# NoiseGen_1.net
KiCad netlist of a schematic drawn in EAGLE
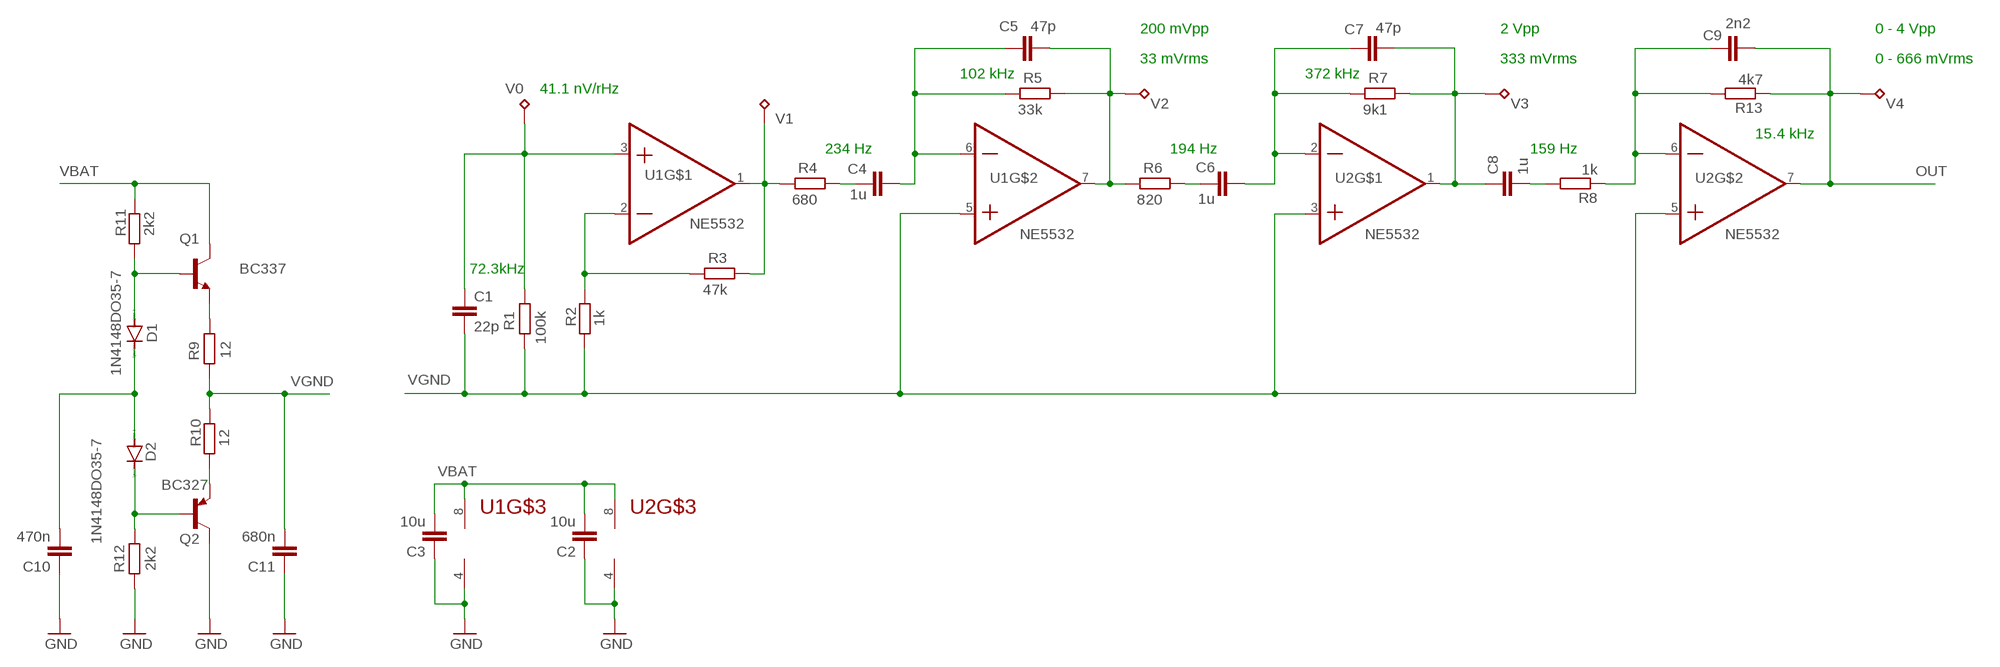
[diagram p0: schematic, sheet 1]

(export (version "E")
  (design (tool "Eeschema 10.0.6"))
  (components
    (comp (ref "C1")
      (value "22p")
      (footprint "eagle-import:C0805")
      (libsource (lib "eagle-import") (part "C-EUC0805"))
    )
    (comp (ref "C2")
      (value "10u")
      (footprint "eagle-import:C0805")
      (libsource (lib "eagle-import") (part "C-EUC0805"))
    )
    (comp (ref "C3")
      (value "10u")
      (footprint "eagle-import:C0805")
      (libsource (lib "eagle-import") (part "C-EUC0805"))
    )
    (comp (ref "C4")
      (value "1u")
      (footprint "eagle-import:C0805")
      (libsource (lib "eagle-import") (part "C-EUC0805"))
    )
    (comp (ref "C5")
      (value "47p")
      (footprint "eagle-import:C0805")
      (libsource (lib "eagle-import") (part "C-EUC0805"))
    )
    (comp (ref "C6")
      (value "1u")
      (footprint "eagle-import:C0805")
      (libsource (lib "eagle-import") (part "C-EUC0805"))
    )
    (comp (ref "C7")
      (value "47p")
      (footprint "eagle-import:C0805")
      (libsource (lib "eagle-import") (part "C-EUC0805"))
    )
    (comp (ref "C8")
      (value "1u")
      (footprint "eagle-import:C0805")
      (libsource (lib "eagle-import") (part "C-EUC0805"))
    )
    (comp (ref "C9")
      (value "2n2")
      (footprint "eagle-import:C0805")
      (libsource (lib "eagle-import") (part "C-EUC0805"))
    )
    (comp (ref "C10")
      (value "470n")
      (footprint "eagle-import:C0805")
      (libsource (lib "eagle-import") (part "C-EUC0805"))
    )
    (comp (ref "C11")
      (value "680n")
      (footprint "eagle-import:C0805")
      (libsource (lib "eagle-import") (part "C-EUC0805"))
    )
    (comp (ref "D1")
      (value "1N4148DO35-7")
      (footprint "eagle-import:DO35-7")
      (libsource (lib "eagle-import") (part "1N4148DO35-7"))
    )
    (comp (ref "D2")
      (value "1N4148DO35-7")
      (footprint "eagle-import:DO35-7")
      (libsource (lib "eagle-import") (part "1N4148DO35-7"))
    )
    (comp (ref "Q1")
      (value "BC337")
      (footprint "eagle-import:TO92")
      (libsource (lib "eagle-import") (part "BC337"))
    )
    (comp (ref "Q2")
      (value "BC327")
      (footprint "eagle-import:TO92")
      (libsource (lib "eagle-import") (part "BC327"))
    )
    (comp (ref "R1")
      (value "100k")
      (footprint "eagle-import:R0805")
      (libsource (lib "eagle-import") (part "R-EU_R0805"))
    )
    (comp (ref "R2")
      (value "1k")
      (footprint "eagle-import:R0805")
      (libsource (lib "eagle-import") (part "R-EU_R0805"))
    )
    (comp (ref "R3")
      (value "47k")
      (footprint "eagle-import:R0805")
      (libsource (lib "eagle-import") (part "R-EU_R0805"))
    )
    (comp (ref "R4")
      (value "680")
      (footprint "eagle-import:R0805")
      (libsource (lib "eagle-import") (part "R-EU_R0805"))
    )
    (comp (ref "R5")
      (value "33k")
      (footprint "eagle-import:R0805")
      (libsource (lib "eagle-import") (part "R-EU_R0805"))
    )
    (comp (ref "R6")
      (value "820")
      (footprint "eagle-import:R0805")
      (libsource (lib "eagle-import") (part "R-EU_R0805"))
    )
    (comp (ref "R7")
      (value "9k1")
      (footprint "eagle-import:R0805")
      (libsource (lib "eagle-import") (part "R-EU_R0805"))
    )
    (comp (ref "R8")
      (value "1k")
      (footprint "eagle-import:R0805")
      (libsource (lib "eagle-import") (part "R-EU_R0805"))
    )
    (comp (ref "R9")
      (value "12")
      (footprint "eagle-import:R0805")
      (libsource (lib "eagle-import") (part "R-EU_R0805"))
    )
    (comp (ref "R10")
      (value "12")
      (footprint "eagle-import:R0805")
      (libsource (lib "eagle-import") (part "R-EU_R0805"))
    )
    (comp (ref "R11")
      (value "2k2")
      (footprint "eagle-import:R0805")
      (libsource (lib "eagle-import") (part "R-EU_R0805"))
    )
    (comp (ref "R12")
      (value "2k2")
      (footprint "eagle-import:R0805")
      (libsource (lib "eagle-import") (part "R-EU_R0805"))
    )
    (comp (ref "R13")
      (value "4k7")
      (footprint "eagle-import:R0805")
      (libsource (lib "eagle-import") (part "R-EU_R0805"))
    )
    (comp (ref "U1")
      (value "NE5532")
      (footprint "eagle-import:DIL-8")
      (libsource (lib "eagle-import") (part "NE5532"))
    )
    (comp (ref "U2")
      (value "NE5532")
      (footprint "eagle-import:DIL-8")
      (libsource (lib "eagle-import") (part "NE5532"))
    )
    (comp (ref "V0")
      (value "TESTPAD")
      (footprint "eagle-import:TESTPAD")
      (libsource (lib "eagle-import") (part "TESTPAD"))
    )
    (comp (ref "V1")
      (value "TESTPAD")
      (footprint "eagle-import:TESTPAD")
      (libsource (lib "eagle-import") (part "TESTPAD"))
    )
    (comp (ref "V2")
      (value "TESTPAD")
      (footprint "eagle-import:TESTPAD")
      (libsource (lib "eagle-import") (part "TESTPAD"))
    )
    (comp (ref "V3")
      (value "TESTPAD")
      (footprint "eagle-import:TESTPAD")
      (libsource (lib "eagle-import") (part "TESTPAD"))
    )
    (comp (ref "V4")
      (value "TESTPAD")
      (footprint "eagle-import:TESTPAD")
      (libsource (lib "eagle-import") (part "TESTPAD"))
    )
  )
  (nets
    (net (code "1") (name "/OUT") (class "Default")
      (node (ref "C9") (pin "2") (pinfunction "2_2") (pintype "passive"))
      (node (ref "R13") (pin "1") (pinfunction "1_1") (pintype "passive"))
      (node (ref "U2") (pin "7") (pinfunction "OUT_7") (pintype "output"))
      (node (ref "V4") (pin "P$1") (pinfunction "TP_P$1") (pintype "input"))
    )
    (net (code "2") (name "/VBAT") (class "Default")
      (node (ref "C2") (pin "2") (pinfunction "2_2") (pintype "passive"))
      (node (ref "C3") (pin "2") (pinfunction "2_2") (pintype "passive"))
      (node (ref "Q1") (pin "3") (pinfunction "C_3") (pintype "passive"))
      (node (ref "R11") (pin "1") (pinfunction "1_1") (pintype "passive"))
      (node (ref "U1") (pin "8") (pinfunction "VP_8") (pintype "bidirectional"))
      (node (ref "U2") (pin "8") (pinfunction "VP_8") (pintype "bidirectional"))
    )
    (net (code "3") (name "/VGND") (class "Default")
      (node (ref "C1") (pin "2") (pinfunction "2_2") (pintype "passive"))
      (node (ref "C11") (pin "2") (pinfunction "2_2") (pintype "passive"))
      (node (ref "R1") (pin "1") (pinfunction "1_1") (pintype "passive"))
      (node (ref "R10") (pin "1") (pinfunction "1_1") (pintype "passive"))
      (node (ref "R2") (pin "1") (pinfunction "1_1") (pintype "passive"))
      (node (ref "R9") (pin "1") (pinfunction "1_1") (pintype "passive"))
      (node (ref "U1") (pin "5") (pinfunction "+IN_5") (pintype "input"))
      (node (ref "U2") (pin "3") (pinfunction "+IN_3") (pintype "input"))
      (node (ref "U2") (pin "5") (pinfunction "+IN_5") (pintype "input"))
    )
    (net (code "4") (name "GND") (class "Default")
      (node (ref "C10") (pin "1") (pinfunction "1_1") (pintype "passive"))
      (node (ref "C11") (pin "1") (pinfunction "1_1") (pintype "passive"))
      (node (ref "C2") (pin "1") (pinfunction "1_1") (pintype "passive"))
      (node (ref "C3") (pin "1") (pinfunction "1_1") (pintype "passive"))
      (node (ref "Q2") (pin "3") (pinfunction "C_3") (pintype "passive"))
      (node (ref "R12") (pin "2") (pinfunction "2_2") (pintype "passive"))
      (node (ref "U1") (pin "4") (pinfunction "VN_4") (pintype "bidirectional"))
      (node (ref "U2") (pin "4") (pinfunction "VN_4") (pintype "bidirectional"))
    )
    (net (code "5") (name "Net-(C4-Pad1)") (class "Default")
      (node (ref "C4") (pin "1") (pinfunction "1_1") (pintype "passive"))
      (node (ref "R4") (pin "1") (pinfunction "1_1") (pintype "passive"))
    )
    (net (code "6") (name "Net-(C6-Pad1)") (class "Default")
      (node (ref "C6") (pin "1") (pinfunction "1_1") (pintype "passive"))
      (node (ref "R6") (pin "1") (pinfunction "1_1") (pintype "passive"))
    )
    (net (code "7") (name "Net-(C8-Pad2)") (class "Default")
      (node (ref "C8") (pin "2") (pinfunction "2_2") (pintype "passive"))
      (node (ref "R8") (pin "2") (pinfunction "2_2") (pintype "passive"))
    )
    (net (code "8") (name "Net-(C10-Pad2)") (class "Default")
      (node (ref "C10") (pin "2") (pinfunction "2_2") (pintype "passive"))
      (node (ref "D1") (pin "C") (pinfunction "C_C") (pintype "passive"))
      (node (ref "D2") (pin "A") (pinfunction "A_A") (pintype "passive"))
    )
    (net (code "9") (name "Net-(Q1-B)") (class "Default")
      (node (ref "D1") (pin "A") (pinfunction "A_A") (pintype "passive"))
      (node (ref "Q1") (pin "2") (pinfunction "B_2") (pintype "passive"))
      (node (ref "R11") (pin "2") (pinfunction "2_2") (pintype "passive"))
    )
    (net (code "10") (name "Net-(Q1-E)") (class "Default")
      (node (ref "Q1") (pin "1") (pinfunction "E_1") (pintype "passive"))
      (node (ref "R9") (pin "2") (pinfunction "2_2") (pintype "passive"))
    )
    (net (code "11") (name "Net-(Q2-B)") (class "Default")
      (node (ref "D2") (pin "C") (pinfunction "C_C") (pintype "passive"))
      (node (ref "Q2") (pin "2") (pinfunction "B_2") (pintype "passive"))
      (node (ref "R12") (pin "1") (pinfunction "1_1") (pintype "passive"))
    )
    (net (code "12") (name "Net-(Q2-E)") (class "Default")
      (node (ref "Q2") (pin "1") (pinfunction "E_1") (pintype "passive"))
      (node (ref "R10") (pin "2") (pinfunction "2_2") (pintype "passive"))
    )
    (net (code "13") (name "Net-(U1A-+IN)") (class "Default")
      (node (ref "C1") (pin "1") (pinfunction "1_1") (pintype "passive"))
      (node (ref "R1") (pin "2") (pinfunction "2_2") (pintype "passive"))
      (node (ref "U1") (pin "3") (pinfunction "+IN_3") (pintype "input"))
      (node (ref "V0") (pin "P$1") (pinfunction "TP_P$1") (pintype "input"))
    )
    (net (code "14") (name "Net-(U1A--IN)") (class "Default")
      (node (ref "R2") (pin "2") (pinfunction "2_2") (pintype "passive"))
      (node (ref "R3") (pin "2") (pinfunction "2_2") (pintype "passive"))
      (node (ref "U1") (pin "2") (pinfunction "-IN_2") (pintype "input"))
    )
    (net (code "15") (name "Net-(U1A-OUT)") (class "Default")
      (node (ref "R3") (pin "1") (pinfunction "1_1") (pintype "passive"))
      (node (ref "R4") (pin "2") (pinfunction "2_2") (pintype "passive"))
      (node (ref "U1") (pin "1") (pinfunction "OUT_1") (pintype "output"))
      (node (ref "V1") (pin "P$1") (pinfunction "TP_P$1") (pintype "input"))
    )
    (net (code "16") (name "Net-(U1B--IN)") (class "Default")
      (node (ref "C4") (pin "2") (pinfunction "2_2") (pintype "passive"))
      (node (ref "C5") (pin "1") (pinfunction "1_1") (pintype "passive"))
      (node (ref "R5") (pin "2") (pinfunction "2_2") (pintype "passive"))
      (node (ref "U1") (pin "6") (pinfunction "-IN_6") (pintype "input"))
    )
    (net (code "17") (name "Net-(U1B-OUT)") (class "Default")
      (node (ref "C5") (pin "2") (pinfunction "2_2") (pintype "passive"))
      (node (ref "R5") (pin "1") (pinfunction "1_1") (pintype "passive"))
      (node (ref "R6") (pin "2") (pinfunction "2_2") (pintype "passive"))
      (node (ref "U1") (pin "7") (pinfunction "OUT_7") (pintype "output"))
      (node (ref "V2") (pin "P$1") (pinfunction "TP_P$1") (pintype "input"))
    )
    (net (code "18") (name "Net-(U2A--IN)") (class "Default")
      (node (ref "C6") (pin "2") (pinfunction "2_2") (pintype "passive"))
      (node (ref "C7") (pin "1") (pinfunction "1_1") (pintype "passive"))
      (node (ref "R7") (pin "2") (pinfunction "2_2") (pintype "passive"))
      (node (ref "U2") (pin "2") (pinfunction "-IN_2") (pintype "input"))
    )
    (net (code "19") (name "Net-(U2A-OUT)") (class "Default")
      (node (ref "C7") (pin "2") (pinfunction "2_2") (pintype "passive"))
      (node (ref "C8") (pin "1") (pinfunction "1_1") (pintype "passive"))
      (node (ref "R7") (pin "1") (pinfunction "1_1") (pintype "passive"))
      (node (ref "U2") (pin "1") (pinfunction "OUT_1") (pintype "output"))
      (node (ref "V3") (pin "P$1") (pinfunction "TP_P$1") (pintype "input"))
    )
    (net (code "20") (name "Net-(U2B--IN)") (class "Default")
      (node (ref "C9") (pin "1") (pinfunction "1_1") (pintype "passive"))
      (node (ref "R13") (pin "2") (pinfunction "2_2") (pintype "passive"))
      (node (ref "R8") (pin "1") (pinfunction "1_1") (pintype "passive"))
      (node (ref "U2") (pin "6") (pinfunction "-IN_6") (pintype "input"))
    )
  )
)
